# untitled.net
KiCad netlist of a schematic drawn in EAGLE
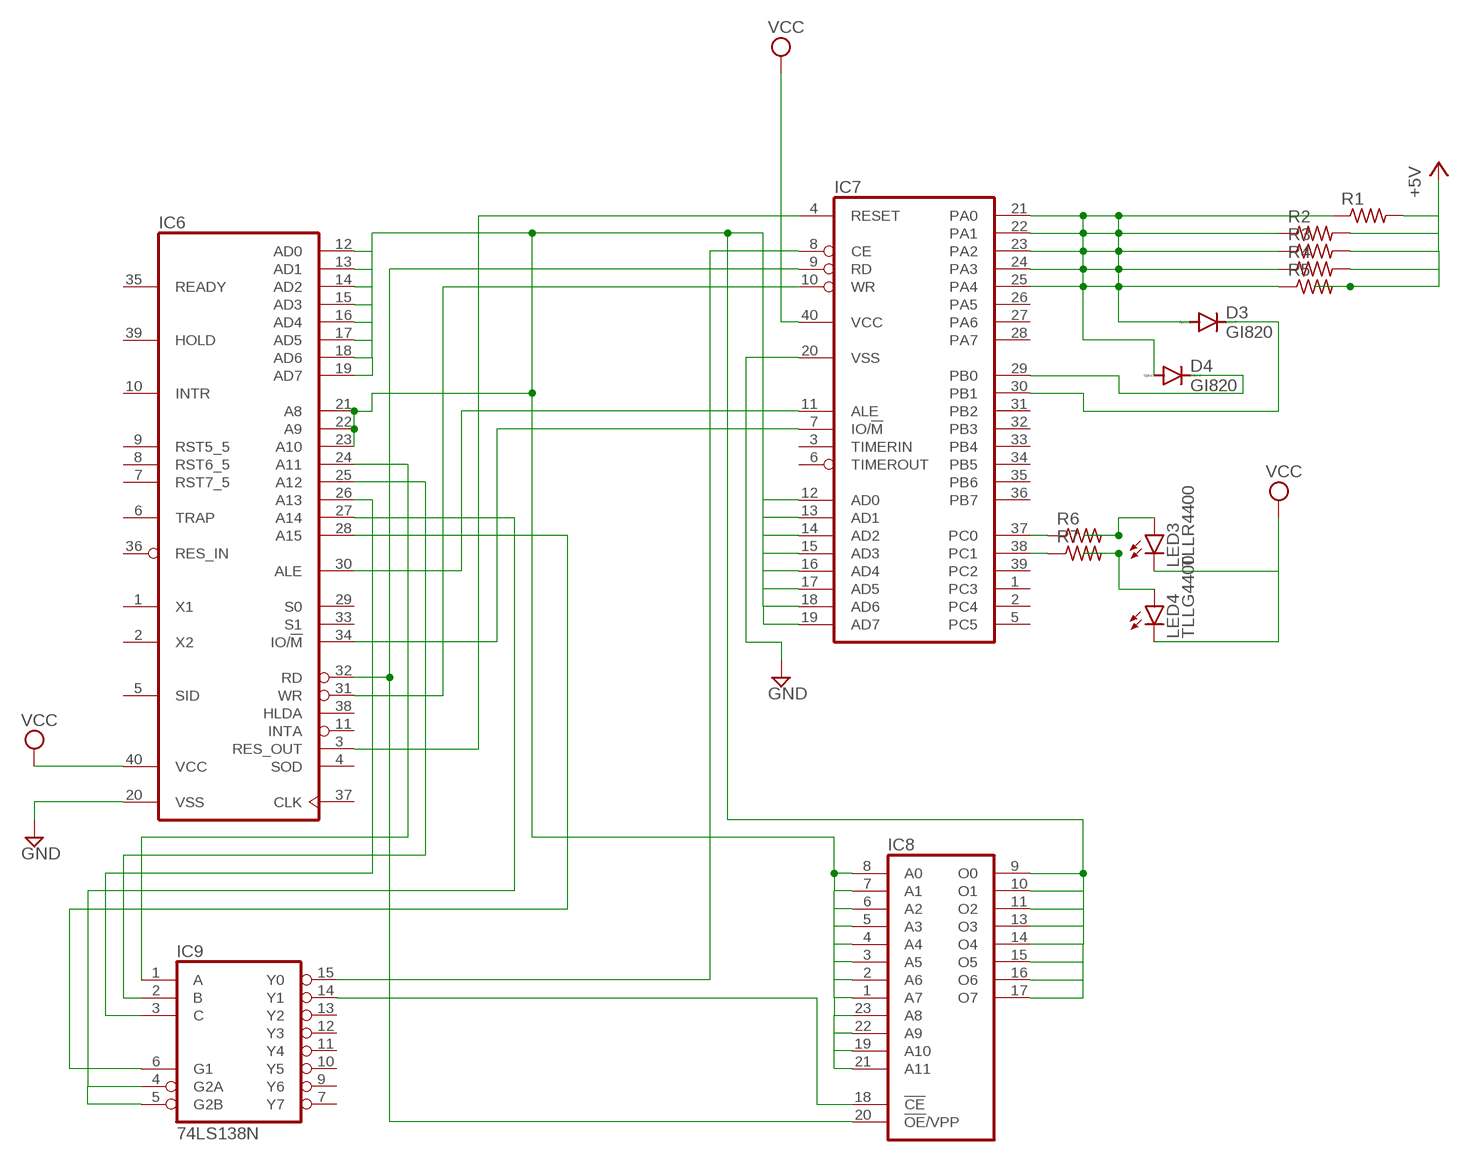
[diagram p0: schematic, sheet 1]

(export (version "E")
  (design (tool "Eeschema 10.0.6"))
  (components
    (comp (ref "D3")
      (value "GI820")
      (footprint "eagle-import:P6-15")
      (libsource (lib "eagle-import") (part "GI820"))
    )
    (comp (ref "D4")
      (value "GI820")
      (footprint "eagle-import:P6-15")
      (libsource (lib "eagle-import") (part "GI820"))
    )
    (comp (ref "IC6")
      (value "8085")
      (footprint "eagle-import:DIL40")
      (libsource (lib "eagle-import") (part "8085"))
    )
    (comp (ref "IC7")
      (value "8155")
      (footprint "eagle-import:DIL40")
      (libsource (lib "eagle-import") (part "8155"))
    )
    (comp (ref "IC8")
      (value "2732")
      (footprint "eagle-import:DIL24")
      (libsource (lib "eagle-import") (part "2732"))
    )
    (comp (ref "IC9")
      (value "74LS138N")
      (footprint "eagle-import:DIL16")
      (libsource (lib "eagle-import") (part "74138NLS"))
    )
    (comp (ref "LED3")
      (value "TLLR4400")
      (footprint "eagle-import:LED3MM")
      (fields (field (name "MF") "VISHAY SEMICONDUCTOR"))
      (libsource (lib "eagle-import") (part "TLLR4400"))
    )
    (comp (ref "LED4")
      (value "TLLG4400")
      (footprint "eagle-import:LED3MM")
      (fields (field (name "MF") "VISHAY SEMICONDUCTOR"))
      (libsource (lib "eagle-import") (part "TLLG4400"))
    )
    (comp (ref "R1")
      (value "R-US_0207/10")
      (footprint "eagle-import:0207_10")
      (libsource (lib "eagle-import") (part "R-US_0207/10"))
    )
    (comp (ref "R2")
      (value "R-US_0207/10")
      (footprint "eagle-import:0207_10")
      (libsource (lib "eagle-import") (part "R-US_0207/10"))
    )
    (comp (ref "R3")
      (value "R-US_0207/10")
      (footprint "eagle-import:0207_10")
      (libsource (lib "eagle-import") (part "R-US_0207/10"))
    )
    (comp (ref "R4")
      (value "R-US_0207/10")
      (footprint "eagle-import:0207_10")
      (libsource (lib "eagle-import") (part "R-US_0207/10"))
    )
    (comp (ref "R5")
      (value "R-US_0207/10")
      (footprint "eagle-import:0207_10")
      (libsource (lib "eagle-import") (part "R-US_0207/10"))
    )
    (comp (ref "R6")
      (value "R-US_0207/10")
      (footprint "eagle-import:0207_10")
      (libsource (lib "eagle-import") (part "R-US_0207/10"))
    )
    (comp (ref "R7")
      (value "R-US_0207/10")
      (footprint "eagle-import:0207_10")
      (libsource (lib "eagle-import") (part "R-US_0207/10"))
    )
  )
  (nets
    (net (code "1") (name "+5V") (class "Default")
      (node (ref "R2") (pin "2") (pinfunction "2_2") (pintype "passive"))
      (node (ref "R3") (pin "2") (pinfunction "2_2") (pintype "passive"))
      (node (ref "R4") (pin "2") (pinfunction "2_2") (pintype "passive"))
      (node (ref "R5") (pin "2") (pinfunction "2_2") (pintype "passive"))
    )
    (net (code "2") (name "GND") (class "Default")
      (node (ref "IC6") (pin "20") (pinfunction "VSS_20") (pintype "power_in"))
      (node (ref "IC7") (pin "20") (pinfunction "VSS_20") (pintype "power_in"))
    )
    (net (code "3") (name "Net-(IC6-A10)") (class "Default")
      (node (ref "IC6") (pin "12") (pinfunction "AD0_12") (pintype "bidirectional"))
      (node (ref "IC6") (pin "13") (pinfunction "AD1_13") (pintype "bidirectional"))
      (node (ref "IC6") (pin "14") (pinfunction "AD2_14") (pintype "bidirectional"))
      (node (ref "IC6") (pin "15") (pinfunction "AD3_15") (pintype "bidirectional"))
      (node (ref "IC6") (pin "16") (pinfunction "AD4_16") (pintype "bidirectional"))
      (node (ref "IC6") (pin "17") (pinfunction "AD5_17") (pintype "bidirectional"))
      (node (ref "IC6") (pin "18") (pinfunction "AD6_18") (pintype "bidirectional"))
      (node (ref "IC6") (pin "19") (pinfunction "AD7_19") (pintype "bidirectional"))
      (node (ref "IC6") (pin "21") (pinfunction "A8_21") (pintype "output"))
      (node (ref "IC6") (pin "22") (pinfunction "A9_22") (pintype "output"))
      (node (ref "IC6") (pin "23") (pinfunction "A10_23") (pintype "output"))
      (node (ref "IC7") (pin "12") (pinfunction "AD0_12") (pintype "bidirectional"))
      (node (ref "IC7") (pin "13") (pinfunction "AD1_13") (pintype "bidirectional"))
      (node (ref "IC7") (pin "14") (pinfunction "AD2_14") (pintype "bidirectional"))
      (node (ref "IC7") (pin "15") (pinfunction "AD3_15") (pintype "bidirectional"))
      (node (ref "IC7") (pin "16") (pinfunction "AD4_16") (pintype "bidirectional"))
      (node (ref "IC7") (pin "17") (pinfunction "AD5_17") (pintype "bidirectional"))
      (node (ref "IC7") (pin "18") (pinfunction "AD6_18") (pintype "bidirectional"))
      (node (ref "IC7") (pin "19") (pinfunction "AD7_19") (pintype "bidirectional"))
      (node (ref "IC8") (pin "1") (pinfunction "A7_1") (pintype "input"))
      (node (ref "IC8") (pin "10") (pinfunction "O1_10") (pintype "tri_state"))
      (node (ref "IC8") (pin "13") (pinfunction "O3_13") (pintype "tri_state"))
      (node (ref "IC8") (pin "19") (pinfunction "A10_19") (pintype "input"))
      (node (ref "IC8") (pin "2") (pinfunction "A6_2") (pintype "input"))
      (node (ref "IC8") (pin "21") (pinfunction "A11_21") (pintype "input"))
      (node (ref "IC8") (pin "22") (pinfunction "A9_22") (pintype "input"))
      (node (ref "IC8") (pin "23") (pinfunction "A8_23") (pintype "input"))
      (node (ref "IC8") (pin "3") (pinfunction "A5_3") (pintype "input"))
      (node (ref "IC8") (pin "4") (pinfunction "A4_4") (pintype "input"))
      (node (ref "IC8") (pin "5") (pinfunction "A3_5") (pintype "input"))
      (node (ref "IC8") (pin "6") (pinfunction "A2_6") (pintype "input"))
      (node (ref "IC8") (pin "7") (pinfunction "A1_7") (pintype "input"))
      (node (ref "IC8") (pin "8") (pinfunction "A0_8") (pintype "input"))
      (node (ref "IC8") (pin "9") (pinfunction "O0_9") (pintype "tri_state"))
    )
    (net (code "4") (name "Net-(IC6-A11)") (class "Default")
      (node (ref "IC6") (pin "24") (pinfunction "A11_24") (pintype "output"))
      (node (ref "IC9") (pin "1") (pinfunction "A_1") (pintype "input"))
    )
    (net (code "5") (name "Net-(IC6-A12)") (class "Default")
      (node (ref "IC6") (pin "25") (pinfunction "A12_25") (pintype "output"))
      (node (ref "IC9") (pin "2") (pinfunction "B_2") (pintype "input"))
    )
    (net (code "6") (name "Net-(IC6-A13)") (class "Default")
      (node (ref "IC6") (pin "26") (pinfunction "A13_26") (pintype "output"))
      (node (ref "IC9") (pin "3") (pinfunction "C_3") (pintype "input"))
    )
    (net (code "7") (name "Net-(IC6-A14)") (class "Default")
      (node (ref "IC6") (pin "27") (pinfunction "A14_27") (pintype "output"))
      (node (ref "IC9") (pin "4") (pinfunction "G2A_4") (pintype "input"))
      (node (ref "IC9") (pin "5") (pinfunction "G2B_5") (pintype "input"))
    )
    (net (code "8") (name "Net-(IC6-A15)") (class "Default")
      (node (ref "IC6") (pin "28") (pinfunction "A15_28") (pintype "output"))
      (node (ref "IC9") (pin "6") (pinfunction "G1_6") (pintype "input"))
    )
    (net (code "9") (name "Net-(IC6-ALE)") (class "Default")
      (node (ref "IC6") (pin "30") (pinfunction "ALE_30") (pintype "output"))
      (node (ref "IC7") (pin "11") (pinfunction "ALE_11") (pintype "input"))
    )
    (net (code "10") (name "Net-(IC6-IO{slash}~{M})") (class "Default")
      (node (ref "IC6") (pin "34") (pinfunction "IO/~{M}_34") (pintype "output"))
      (node (ref "IC7") (pin "7") (pinfunction "IO/~{M}_7") (pintype "input"))
    )
    (net (code "11") (name "Net-(IC6-RD)") (class "Default")
      (node (ref "IC6") (pin "32") (pinfunction "RD_32") (pintype "output"))
      (node (ref "IC7") (pin "9") (pinfunction "RD_9") (pintype "input"))
      (node (ref "IC8") (pin "20") (pinfunction "~{OE}/VPP_20") (pintype "input"))
    )
    (net (code "12") (name "Net-(IC6-RES_OUT)") (class "Default")
      (node (ref "IC6") (pin "3") (pinfunction "RES_OUT_3") (pintype "output"))
      (node (ref "IC7") (pin "4") (pinfunction "RESET_4") (pintype "input"))
    )
    (net (code "13") (name "Net-(IC6-WR)") (class "Default")
      (node (ref "IC6") (pin "31") (pinfunction "WR_31") (pintype "output"))
      (node (ref "IC7") (pin "10") (pinfunction "WR_10") (pintype "input"))
    )
    (net (code "14") (name "Net-(IC7-CE)") (class "Default")
      (node (ref "IC7") (pin "8") (pinfunction "CE_8") (pintype "input"))
      (node (ref "IC9") (pin "15") (pinfunction "Y0_15") (pintype "output"))
    )
    (net (code "15") (name "Net-(IC7-PA0)") (class "Default")
      (node (ref "D3") (pin "A") (pinfunction "A_A") (pintype "passive"))
      (node (ref "D4") (pin "A") (pinfunction "A_A") (pintype "passive"))
      (node (ref "IC7") (pin "21") (pinfunction "PA0_21") (pintype "bidirectional"))
      (node (ref "IC7") (pin "22") (pinfunction "PA1_22") (pintype "bidirectional"))
      (node (ref "IC7") (pin "23") (pinfunction "PA2_23") (pintype "bidirectional"))
      (node (ref "IC7") (pin "24") (pinfunction "PA3_24") (pintype "bidirectional"))
      (node (ref "IC7") (pin "25") (pinfunction "PA4_25") (pintype "bidirectional"))
      (node (ref "R1") (pin "1") (pinfunction "1_1") (pintype "passive"))
      (node (ref "R2") (pin "1") (pinfunction "1_1") (pintype "passive"))
      (node (ref "R3") (pin "1") (pinfunction "1_1") (pintype "passive"))
      (node (ref "R4") (pin "1") (pinfunction "1_1") (pintype "passive"))
      (node (ref "R5") (pin "1") (pinfunction "1_1") (pintype "passive"))
    )
    (net (code "16") (name "Net-(IC7-PB0)") (class "Default")
      (node (ref "D4") (pin "C") (pinfunction "C_C") (pintype "passive"))
      (node (ref "IC7") (pin "29") (pinfunction "PB0_29") (pintype "bidirectional"))
    )
    (net (code "17") (name "Net-(IC7-PB1)") (class "Default")
      (node (ref "D3") (pin "C") (pinfunction "C_C") (pintype "passive"))
      (node (ref "IC7") (pin "30") (pinfunction "PB1_30") (pintype "bidirectional"))
    )
    (net (code "18") (name "Net-(IC7-PC0)") (class "Default")
      (node (ref "IC7") (pin "37") (pinfunction "PC0_37") (pintype "bidirectional"))
      (node (ref "R6") (pin "1") (pinfunction "1_1") (pintype "passive"))
    )
    (net (code "19") (name "Net-(IC7-PC1)") (class "Default")
      (node (ref "IC7") (pin "38") (pinfunction "PC1_38") (pintype "bidirectional"))
      (node (ref "R7") (pin "1") (pinfunction "1_1") (pintype "passive"))
    )
    (net (code "20") (name "Net-(IC8A-O2)") (class "Default")
      (node (ref "IC8") (pin "11") (pinfunction "O2_11") (pintype "tri_state"))
      (node (ref "IC8") (pin "14") (pinfunction "O4_14") (pintype "tri_state"))
      (node (ref "IC8") (pin "15") (pinfunction "O5_15") (pintype "tri_state"))
      (node (ref "IC8") (pin "16") (pinfunction "O6_16") (pintype "tri_state"))
      (node (ref "IC8") (pin "17") (pinfunction "O7_17") (pintype "tri_state"))
    )
    (net (code "21") (name "Net-(IC8A-~{CE})") (class "Default")
      (node (ref "IC8") (pin "18") (pinfunction "~{CE}_18") (pintype "input"))
      (node (ref "IC9") (pin "14") (pinfunction "Y1_14") (pintype "output"))
    )
    (net (code "22") (name "Net-(LED3-PadA)") (class "Default")
      (node (ref "LED3") (pin "A") (pinfunction "A_A") (pintype "passive"))
      (node (ref "R6") (pin "2") (pinfunction "2_2") (pintype "passive"))
    )
    (net (code "23") (name "Net-(LED4-PadA)") (class "Default")
      (node (ref "LED4") (pin "A") (pinfunction "A_A") (pintype "passive"))
      (node (ref "R7") (pin "2") (pinfunction "2_2") (pintype "passive"))
    )
    (net (code "24") (name "VCC") (class "Default")
      (node (ref "IC6") (pin "40") (pinfunction "VCC_40") (pintype "power_in"))
      (node (ref "IC7") (pin "40") (pinfunction "VCC_40") (pintype "power_in"))
      (node (ref "LED3") (pin "K") (pinfunction "C_K") (pintype "passive"))
      (node (ref "LED4") (pin "K") (pinfunction "C_K") (pintype "passive"))
    )
    (net (code "25") (name "unconnected-(IC6-CLK-Pad37)") (class "Default")
      (node (ref "IC6") (pin "37") (pinfunction "CLK_37") (pintype "output"))
    )
    (net (code "26") (name "unconnected-(IC6-HLDA-Pad38)") (class "Default")
      (node (ref "IC6") (pin "38") (pinfunction "HLDA_38") (pintype "output"))
    )
    (net (code "27") (name "unconnected-(IC6-HOLD-Pad39)") (class "Default")
      (node (ref "IC6") (pin "39") (pinfunction "HOLD_39") (pintype "input"))
    )
    (net (code "28") (name "unconnected-(IC6-INTA-Pad11)") (class "Default")
      (node (ref "IC6") (pin "11") (pinfunction "INTA_11") (pintype "output"))
    )
    (net (code "29") (name "unconnected-(IC6-INTR-Pad10)") (class "Default")
      (node (ref "IC6") (pin "10") (pinfunction "INTR_10") (pintype "input"))
    )
    (net (code "30") (name "unconnected-(IC6-READY-Pad35)") (class "Default")
      (node (ref "IC6") (pin "35") (pinfunction "READY_35") (pintype "input"))
    )
    (net (code "31") (name "unconnected-(IC6-RES_IN-Pad36)") (class "Default")
      (node (ref "IC6") (pin "36") (pinfunction "RES_IN_36") (pintype "input"))
    )
    (net (code "32") (name "unconnected-(IC6-RST5_5-Pad9)") (class "Default")
      (node (ref "IC6") (pin "9") (pinfunction "RST5_5_9") (pintype "input"))
    )
    (net (code "33") (name "unconnected-(IC6-RST6_5-Pad8)") (class "Default")
      (node (ref "IC6") (pin "8") (pinfunction "RST6_5_8") (pintype "input"))
    )
    (net (code "34") (name "unconnected-(IC6-RST7_5-Pad7)") (class "Default")
      (node (ref "IC6") (pin "7") (pinfunction "RST7_5_7") (pintype "input"))
    )
    (net (code "35") (name "unconnected-(IC6-S0-Pad29)") (class "Default")
      (node (ref "IC6") (pin "29") (pinfunction "S0_29") (pintype "output"))
    )
    (net (code "36") (name "unconnected-(IC6-S1-Pad33)") (class "Default")
      (node (ref "IC6") (pin "33") (pinfunction "S1_33") (pintype "output"))
    )
    (net (code "37") (name "unconnected-(IC6-SID-Pad5)") (class "Default")
      (node (ref "IC6") (pin "5") (pinfunction "SID_5") (pintype "input"))
    )
    (net (code "38") (name "unconnected-(IC6-SOD-Pad4)") (class "Default")
      (node (ref "IC6") (pin "4") (pinfunction "SOD_4") (pintype "output"))
    )
    (net (code "39") (name "unconnected-(IC6-TRAP-Pad6)") (class "Default")
      (node (ref "IC6") (pin "6") (pinfunction "TRAP_6") (pintype "input"))
    )
    (net (code "40") (name "unconnected-(IC6-X1-Pad1)") (class "Default")
      (node (ref "IC6") (pin "1") (pinfunction "X1_1") (pintype "input"))
    )
    (net (code "41") (name "unconnected-(IC6-X2-Pad2)") (class "Default")
      (node (ref "IC6") (pin "2") (pinfunction "X2_2") (pintype "input"))
    )
    (net (code "42") (name "unconnected-(IC7-PA5-Pad26)") (class "Default")
      (node (ref "IC7") (pin "26") (pinfunction "PA5_26") (pintype "bidirectional"))
    )
    (net (code "43") (name "unconnected-(IC7-PA6-Pad27)") (class "Default")
      (node (ref "IC7") (pin "27") (pinfunction "PA6_27") (pintype "bidirectional"))
    )
    (net (code "44") (name "unconnected-(IC7-PA7-Pad28)") (class "Default")
      (node (ref "IC7") (pin "28") (pinfunction "PA7_28") (pintype "bidirectional"))
    )
    (net (code "45") (name "unconnected-(IC7-PB2-Pad31)") (class "Default")
      (node (ref "IC7") (pin "31") (pinfunction "PB2_31") (pintype "bidirectional"))
    )
    (net (code "46") (name "unconnected-(IC7-PB3-Pad32)") (class "Default")
      (node (ref "IC7") (pin "32") (pinfunction "PB3_32") (pintype "bidirectional"))
    )
    (net (code "47") (name "unconnected-(IC7-PB4-Pad33)") (class "Default")
      (node (ref "IC7") (pin "33") (pinfunction "PB4_33") (pintype "bidirectional"))
    )
    (net (code "48") (name "unconnected-(IC7-PB5-Pad34)") (class "Default")
      (node (ref "IC7") (pin "34") (pinfunction "PB5_34") (pintype "bidirectional"))
    )
    (net (code "49") (name "unconnected-(IC7-PB6-Pad35)") (class "Default")
      (node (ref "IC7") (pin "35") (pinfunction "PB6_35") (pintype "bidirectional"))
    )
    (net (code "50") (name "unconnected-(IC7-PB7-Pad36)") (class "Default")
      (node (ref "IC7") (pin "36") (pinfunction "PB7_36") (pintype "bidirectional"))
    )
    (net (code "51") (name "unconnected-(IC7-PC2-Pad39)") (class "Default")
      (node (ref "IC7") (pin "39") (pinfunction "PC2_39") (pintype "bidirectional"))
    )
    (net (code "52") (name "unconnected-(IC7-PC3-Pad1)") (class "Default")
      (node (ref "IC7") (pin "1") (pinfunction "PC3_1") (pintype "bidirectional"))
    )
    (net (code "53") (name "unconnected-(IC7-PC4-Pad2)") (class "Default")
      (node (ref "IC7") (pin "2") (pinfunction "PC4_2") (pintype "bidirectional"))
    )
    (net (code "54") (name "unconnected-(IC7-PC5-Pad5)") (class "Default")
      (node (ref "IC7") (pin "5") (pinfunction "PC5_5") (pintype "bidirectional"))
    )
    (net (code "55") (name "unconnected-(IC7-TIMERIN-Pad3)") (class "Default")
      (node (ref "IC7") (pin "3") (pinfunction "TIMERIN_3") (pintype "input"))
    )
    (net (code "56") (name "unconnected-(IC7-TIMEROUT-Pad6)") (class "Default")
      (node (ref "IC7") (pin "6") (pinfunction "TIMEROUT_6") (pintype "output"))
    )
    (net (code "57") (name "unconnected-(IC9A-Y2-Pad13)") (class "Default")
      (node (ref "IC9") (pin "13") (pinfunction "Y2_13") (pintype "output"))
    )
    (net (code "58") (name "unconnected-(IC9A-Y3-Pad12)") (class "Default")
      (node (ref "IC9") (pin "12") (pinfunction "Y3_12") (pintype "output"))
    )
    (net (code "59") (name "unconnected-(IC9A-Y4-Pad11)") (class "Default")
      (node (ref "IC9") (pin "11") (pinfunction "Y4_11") (pintype "output"))
    )
    (net (code "60") (name "unconnected-(IC9A-Y5-Pad10)") (class "Default")
      (node (ref "IC9") (pin "10") (pinfunction "Y5_10") (pintype "output"))
    )
    (net (code "61") (name "unconnected-(IC9A-Y6-Pad9)") (class "Default")
      (node (ref "IC9") (pin "9") (pinfunction "Y6_9") (pintype "output"))
    )
    (net (code "62") (name "unconnected-(IC9A-Y7-Pad7)") (class "Default")
      (node (ref "IC9") (pin "7") (pinfunction "Y7_7") (pintype "output"))
    )
    (net (code "63") (name "unconnected-(R1-Pad2)") (class "Default")
      (node (ref "R1") (pin "2") (pinfunction "2_2") (pintype "passive"))
    )
  )
)
